# Ground_Station.net
KiCad netlist of a schematic drawn in EasyEDA
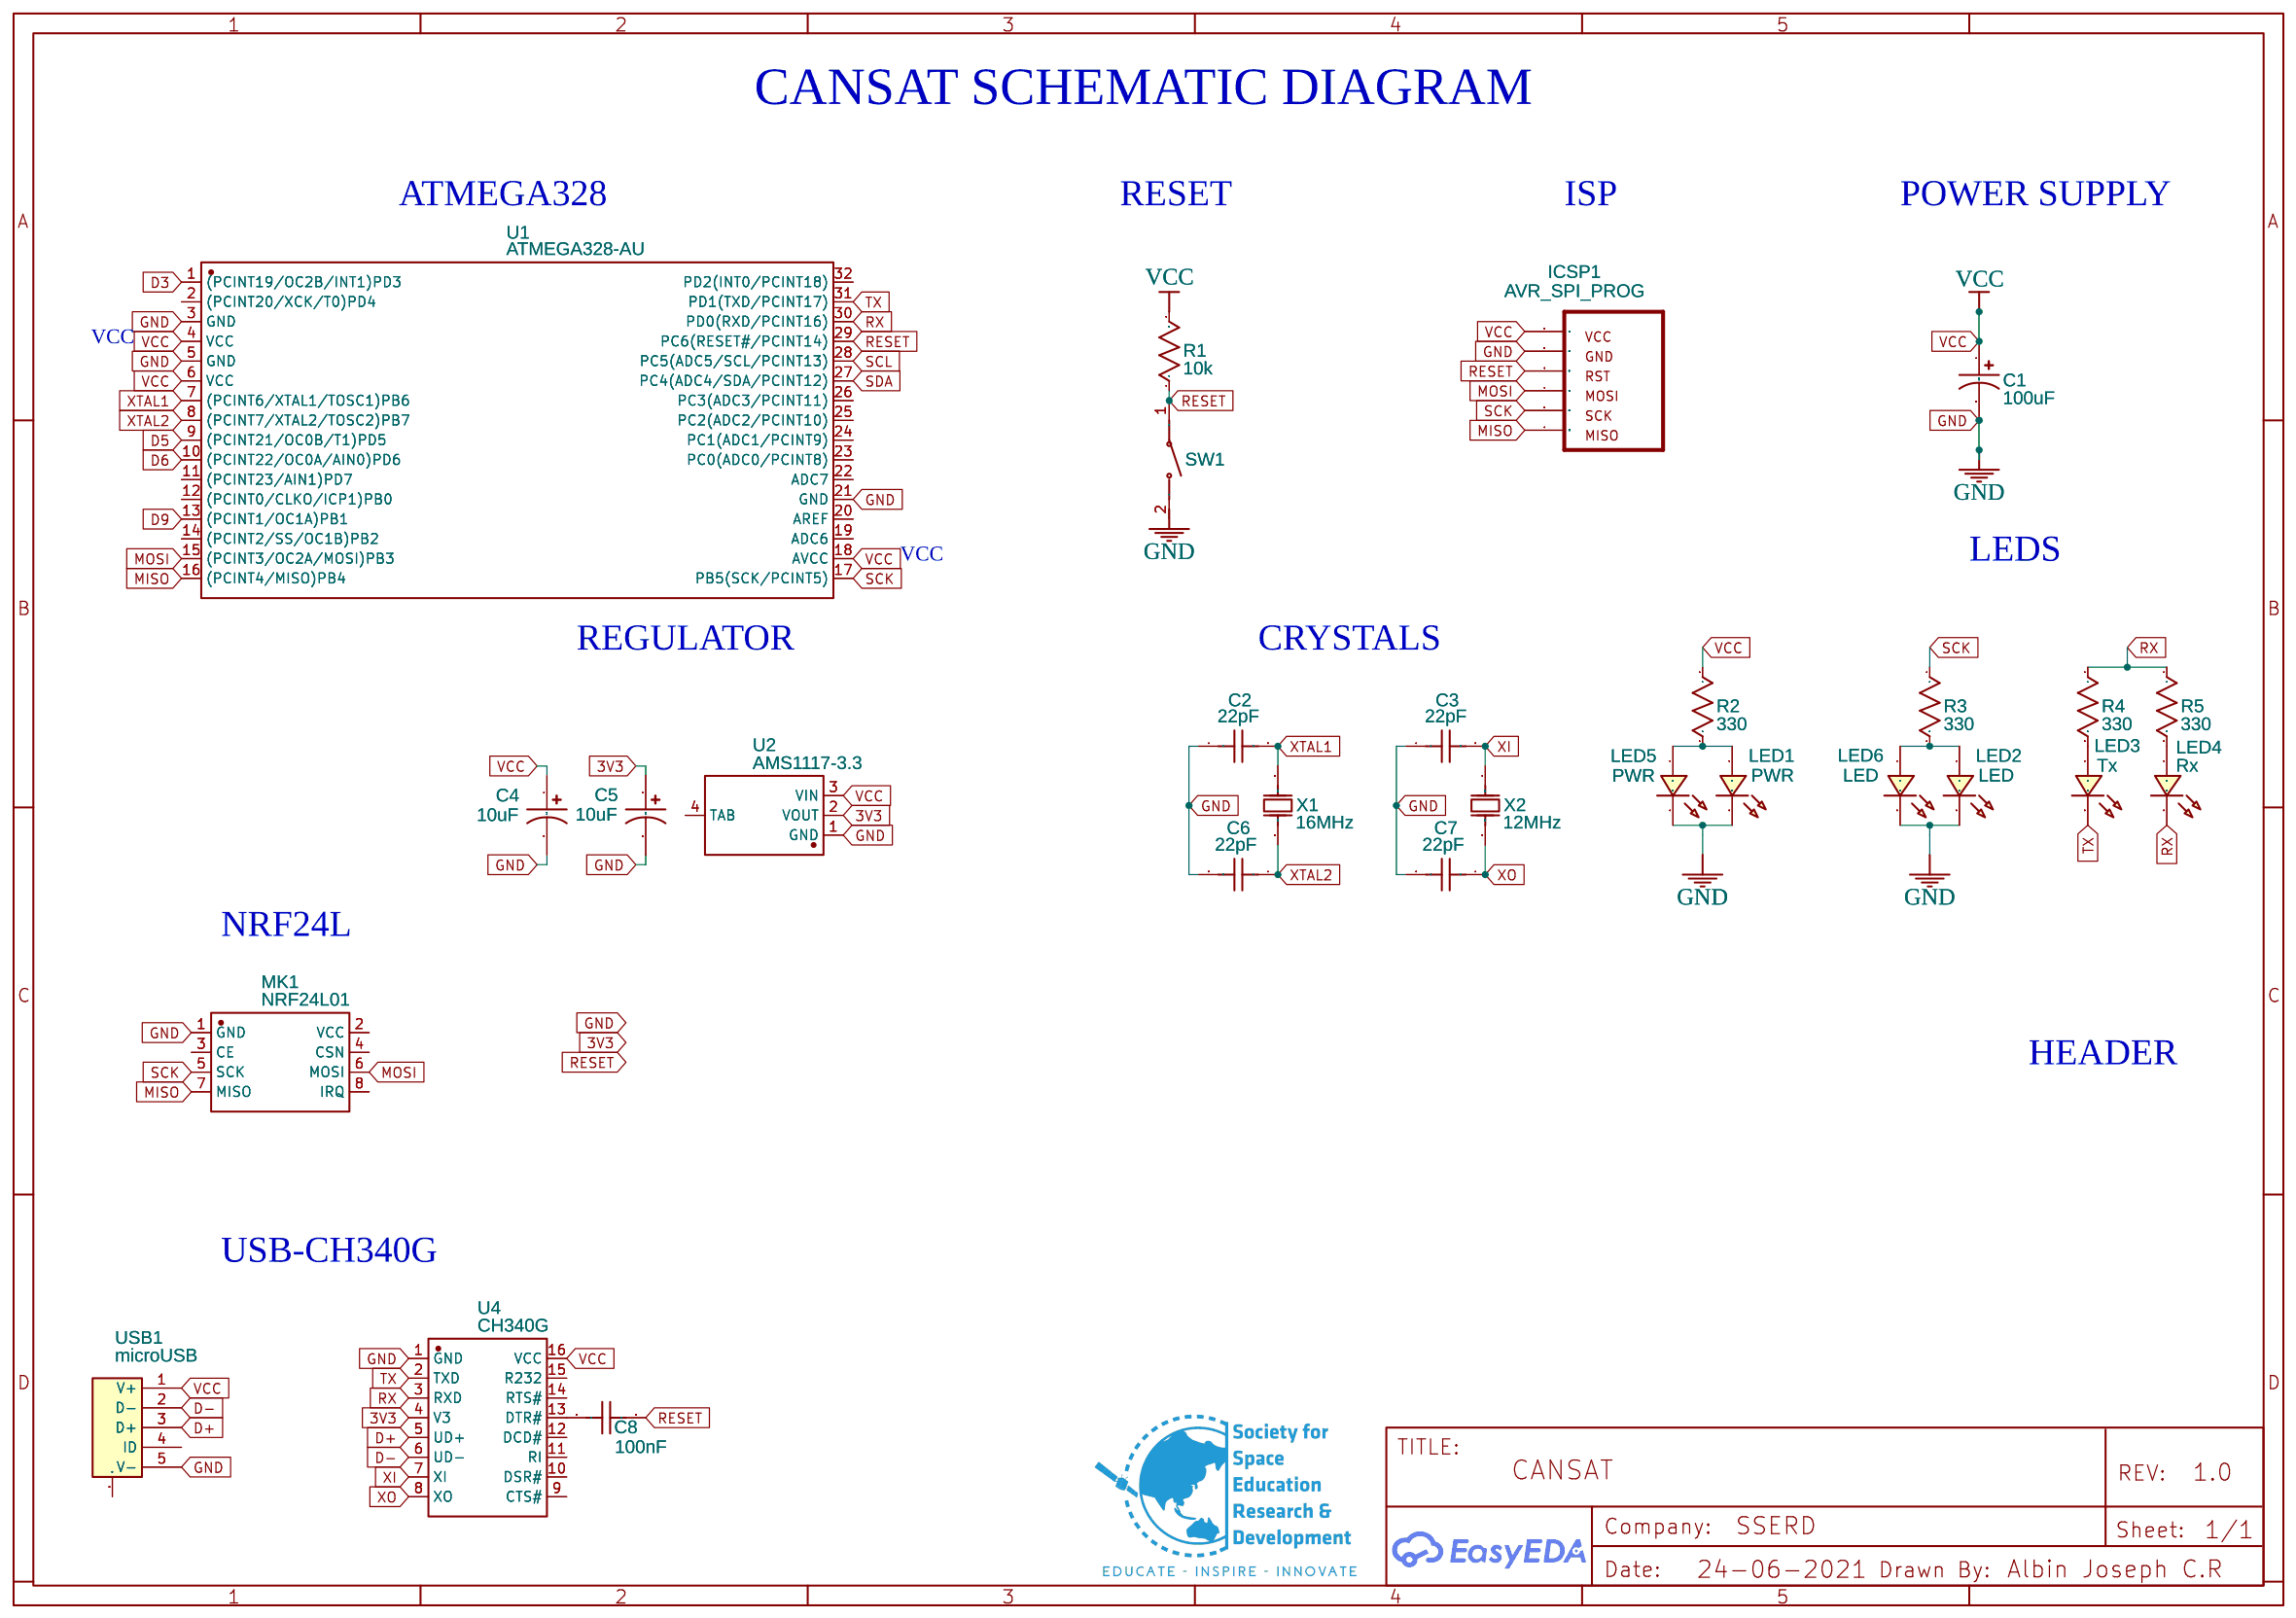
[diagram p0: schematic sheet]

(export (version "E")
  (design (tool "Eeschema 10.0.6"))
  (components
    (comp (ref "C1") (value "100uF") (libsource (lib "") (part "CE_TH_D4.0×F1.5_US")))
    (comp (ref "C2")
      (value "22pF")
      (fields
        (field (name "BOM_Manufacturer Part") "CC1H0R5CA1BDCH4B10MF")
        (field (name "BOM_Supplier Part") "C254078")
      )
      (libsource (lib "") (part "CC1H0R5CA1BDCH4B10MF_1"))
    )
    (comp (ref "C3")
      (value "22pF")
      (fields
        (field (name "BOM_Manufacturer Part") "CC1H0R5CA1BDCH4B10MF")
        (field (name "BOM_Supplier Part") "C254078")
      )
      (libsource (lib "") (part "CC1H0R5CA1BDCH4B10MF_1"))
    )
    (comp (ref "C4") (value "10uF") (libsource (lib "") (part "CE_TH_D4.0×F1.5_US")))
    (comp (ref "C5") (value "10uF") (libsource (lib "") (part "CE_TH_D4.0×F1.5_US")))
    (comp (ref "C6")
      (value "22pF")
      (fields
        (field (name "BOM_Manufacturer Part") "CC1H0R5CA1BDCH4B10MF")
        (field (name "BOM_Supplier Part") "C254078")
      )
      (libsource (lib "") (part "CC1H0R5CA1BDCH4B10MF"))
    )
    (comp (ref "C7")
      (value "22pF")
      (fields
        (field (name "BOM_Manufacturer Part") "CC1H0R5CA1BDCH4B10MF")
        (field (name "BOM_Supplier Part") "C254078")
      )
      (libsource (lib "") (part "CC1H0R5CA1BDCH4B10MF"))
    )
    (comp (ref "C8")
      (value "100nF")
      (fields
        (field (name "BOM_Manufacturer Part") "CC1H0R5CA1BDCH4B10MF")
        (field (name "BOM_Supplier Part") "C254078")
      )
      (libsource (lib "") (part "CC1H0R5CA1BDCH4B10MF_1"))
    )
    (comp (ref "ICSP1") (value "AVR_SPI_PROG") (libsource (lib "") (part "PA_AVR_SPI_PROGRAMMER_ARDUINO")))
    (comp (ref "LED1")
      (value "PWR")
      (fields (field (name "BOM_Manufacturer Part") "NCD0805G1") (field (name "BOM_Supplier Part") "C84260"))
      (libsource (lib "") (part "LED-0805_G"))
    )
    (comp (ref "LED2")
      (value "LED")
      (fields (field (name "BOM_Manufacturer Part") "NCD0805G1") (field (name "BOM_Supplier Part") "C84260"))
      (libsource (lib "") (part "LED-0805_G"))
    )
    (comp (ref "LED3")
      (value "Tx")
      (fields
        (field (name "BOM_Manufacturer Part") "D-B080508B1-KS2")
        (field (name "BOM_Supplier Part") "C108412")
      )
      (libsource (lib "") (part "LED-0805_B"))
    )
    (comp (ref "LED4")
      (value "Rx")
      (fields
        (field (name "BOM_Manufacturer Part") "D-B080508B1-KS2")
        (field (name "BOM_Supplier Part") "C108412")
      )
      (libsource (lib "") (part "LED-0805_B"))
    )
    (comp (ref "LED5")
      (value "PWR")
      (fields
        (field (name "BOM_Manufacturer Part") "204-10SYGD/S530-E3")
        (field (name "BOM_Supplier Part") "C85161")
      )
      (libsource (lib "") (part "LED-TH-3mm_G"))
    )
    (comp (ref "LED6")
      (value "LED")
      (fields
        (field (name "BOM_Manufacturer Part") "204-10SYGD/S530-E3")
        (field (name "BOM_Supplier Part") "C85161")
      )
      (libsource (lib "") (part "LED-TH-3mm_G"))
    )
    (comp (ref "MK1")
      (value "NRF24L01")
      (fields
        (field (name "BOM_Manufacturer Part") "NRF24L01+功率加强版绑定2.4Gwireless module")
        (field (name "BOM_Supplier Part") "C90751")
      )
      (libsource (lib "") (part "NRF24L01"))
    )
    (comp (ref "R1") (value "10k") (libsource (lib "") (part "R_AXIAL-0.4_US")))
    (comp (ref "R2") (value "330") (libsource (lib "") (part "R_AXIAL-0.4_US_1")))
    (comp (ref "R3") (value "330") (libsource (lib "") (part "R_AXIAL-0.4_US_1")))
    (comp (ref "R4") (value "330") (libsource (lib "") (part "R_AXIAL-0.4_US_1")))
    (comp (ref "R5") (value "330") (libsource (lib "") (part "R_AXIAL-0.4_US_1")))
    (comp (ref "SW1")
      (value "SWITCH,3*6*2.5")
      (fields
        (field (name "BOM_Manufacturer Part") "Switch,3*6*5Plastic head white,260G, 0.25mm,SMD")
        (field (name "BOM_Supplier Part") "C71855")
      )
      (libsource (lib "") (part "SWITCH,3*6*5PLASTIC HEAD WHITE,260G, 0.25MM,SMD"))
    )
    (comp (ref "U1")
      (value "ATMEGA328-AU")
      (fields (field (name "BOM_Supplier Part") "C618731"))
      (libsource (lib "") (part "ATMEGA328-AU"))
    )
    (comp (ref "U2")
      (value "AMS1117-3.3")
      (fields
        (field (name "BOM_Manufacturer Part") "AMS1117-1.8")
        (field (name "BOM_Supplier Part") "C498120")
      )
      (libsource (lib "") (part "AMS1117-1.8_C498120"))
    )
    (comp (ref "U4")
      (value "CH340G")
      (fields (field (name "BOM_Supplier Part") "C14267"))
      (libsource (lib "") (part "CH340G"))
    )
    (comp (ref "USB1")
      (value "microUSB")
      (fields
        (field (name "BOM_Manufacturer Part") "micro USBFemale")
        (field (name "BOM_Supplier Part") "C10418")
      )
      (libsource (lib "") (part "micro USBFemale"))
    )
    (comp (ref "X1")
      (value "16MHz")
      (fields
        (field (name "BOM_Manufacturer Part") "9AC10000202060")
        (field (name "BOM_Supplier Part") "C1508959")
      )
      (libsource (lib "") (part "9AC10000202060"))
    )
    (comp (ref "X2")
      (value "12MHz")
      (fields
        (field (name "BOM_Manufacturer Part") "9AC10000202060")
        (field (name "BOM_Supplier Part") "C1508959")
      )
      (libsource (lib "") (part "9AC10000202060"))
    )
  )
  (nets
    (net (code "1") (name "3V3") (class "Default")
      (node (ref "C5") (pin "1") (pinfunction "1_1") (pintype "unspecified"))
      (node (ref "U2") (pin "2") (pinfunction "VOUT_2") (pintype "unspecified"))
      (node (ref "U4") (pin "4") (pinfunction "V3_4") (pintype "unspecified"))
    )
    (net (code "2") (name "D+") (class "Default")
      (node (ref "U4") (pin "5") (pinfunction "UD+_5") (pintype "unspecified"))
      (node (ref "USB1") (pin "3") (pinfunction "D+_3") (pintype "unspecified"))
    )
    (net (code "3") (name "D-") (class "Default")
      (node (ref "U4") (pin "6") (pinfunction "UD-_6") (pintype "unspecified"))
      (node (ref "USB1") (pin "2") (pinfunction "D-_2") (pintype "unspecified"))
    )
    (net (code "4") (name "D3") (class "Default")
      (node (ref "U1") (pin "1") (pinfunction "(PCINT19/OC2B/INT1)PD3_1") (pintype "unspecified"))
    )
    (net (code "5") (name "D5") (class "Default")
      (node (ref "U1") (pin "9") (pinfunction "(PCINT21/OC0B/T1)PD5_9") (pintype "unspecified"))
    )
    (net (code "6") (name "D6") (class "Default")
      (node (ref "U1") (pin "10") (pinfunction "(PCINT22/OC0A/AIN0)PD6_10") (pintype "unspecified"))
    )
    (net (code "7") (name "D9") (class "Default")
      (node (ref "U1") (pin "13") (pinfunction "(PCINT1/OC1A)PB1_13") (pintype "unspecified"))
    )
    (net (code "8") (name "GND") (class "Default")
      (node (ref "C1") (pin "2") (pinfunction "2_2") (pintype "unspecified"))
      (node (ref "C2") (pin "1") (pinfunction "1_1") (pintype "unspecified"))
      (node (ref "C3") (pin "1") (pinfunction "1_1") (pintype "unspecified"))
      (node (ref "C4") (pin "2") (pinfunction "2_2") (pintype "unspecified"))
      (node (ref "C5") (pin "2") (pinfunction "2_2") (pintype "unspecified"))
      (node (ref "C6") (pin "2") (pinfunction "2_2") (pintype "unspecified"))
      (node (ref "C7") (pin "2") (pinfunction "2_2") (pintype "unspecified"))
      (node (ref "ICSP1") (pin "6") (pinfunction "GND_6") (pintype "unspecified"))
      (node (ref "LED1") (pin "2") (pinfunction "2_2") (pintype "unspecified"))
      (node (ref "LED2") (pin "2") (pinfunction "2_2") (pintype "unspecified"))
      (node (ref "LED5") (pin "2") (pinfunction "2_2") (pintype "unspecified"))
      (node (ref "LED6") (pin "2") (pinfunction "2_2") (pintype "unspecified"))
      (node (ref "MK1") (pin "1") (pinfunction "GND_1") (pintype "unspecified"))
      (node (ref "SW1") (pin "2") (pinfunction "2_2") (pintype "unspecified"))
      (node (ref "U1") (pin "21") (pinfunction "GND_21") (pintype "unspecified"))
      (node (ref "U1") (pin "3") (pinfunction "GND_3") (pintype "unspecified"))
      (node (ref "U1") (pin "5") (pinfunction "GND_5") (pintype "unspecified"))
      (node (ref "U2") (pin "1") (pinfunction "GND_1") (pintype "unspecified"))
      (node (ref "U4") (pin "1") (pinfunction "GND_1") (pintype "unspecified"))
      (node (ref "USB1") (pin "5") (pinfunction "V-_5") (pintype "unspecified"))
    )
    (net (code "9") (name "MISO") (class "Default")
      (node (ref "ICSP1") (pin "1") (pinfunction "MISO_1") (pintype "unspecified"))
      (node (ref "MK1") (pin "7") (pinfunction "MISO_7") (pintype "unspecified"))
      (node (ref "U1") (pin "16") (pinfunction "(PCINT4/MISO)PB4_16") (pintype "unspecified"))
    )
    (net (code "10") (name "MOSI") (class "Default")
      (node (ref "ICSP1") (pin "4") (pinfunction "MOSI_4") (pintype "unspecified"))
      (node (ref "MK1") (pin "6") (pinfunction "MOSI_6") (pintype "unspecified"))
      (node (ref "U1") (pin "15") (pinfunction "(PCINT3/OC2A/MOSI)PB3_15") (pintype "unspecified"))
    )
    (net (code "11") (name "Net-(LED1-Pad1)") (class "Default")
      (node (ref "LED1") (pin "1") (pinfunction "1_1") (pintype "unspecified"))
      (node (ref "LED5") (pin "1") (pinfunction "1_1") (pintype "unspecified"))
      (node (ref "R2") (pin "2") (pinfunction "2_2") (pintype "unspecified"))
    )
    (net (code "12") (name "Net-(LED2-Pad1)") (class "Default")
      (node (ref "LED2") (pin "1") (pinfunction "1_1") (pintype "unspecified"))
      (node (ref "LED6") (pin "1") (pinfunction "1_1") (pintype "unspecified"))
      (node (ref "R3") (pin "2") (pinfunction "2_2") (pintype "unspecified"))
    )
    (net (code "13") (name "Net-(LED3-Pad1)") (class "Default")
      (node (ref "LED3") (pin "1") (pinfunction "1_1") (pintype "unspecified"))
      (node (ref "R4") (pin "2") (pinfunction "2_2") (pintype "unspecified"))
    )
    (net (code "14") (name "Net-(LED4-Pad1)") (class "Default")
      (node (ref "LED4") (pin "1") (pinfunction "1_1") (pintype "unspecified"))
      (node (ref "R5") (pin "2") (pinfunction "2_2") (pintype "unspecified"))
    )
    (net (code "15") (name "Net-(U4-DTR#)") (class "Default")
      (node (ref "C8") (pin "1") (pinfunction "1_1") (pintype "unspecified"))
      (node (ref "U4") (pin "13") (pinfunction "DTR#_13") (pintype "unspecified"))
    )
    (net (code "16") (name "RESET") (class "Default")
      (node (ref "C8") (pin "2") (pinfunction "2_2") (pintype "unspecified"))
      (node (ref "ICSP1") (pin "5") (pinfunction "RST_5") (pintype "unspecified"))
      (node (ref "R1") (pin "1") (pinfunction "1_1") (pintype "unspecified"))
      (node (ref "SW1") (pin "1") (pinfunction "1_1") (pintype "unspecified"))
      (node (ref "U1") (pin "29") (pinfunction "PC6(RESET#/PCINT14)_29") (pintype "unspecified"))
    )
    (net (code "17") (name "RX") (class "Default")
      (node (ref "LED4") (pin "2") (pinfunction "2_2") (pintype "unspecified"))
      (node (ref "R4") (pin "1") (pinfunction "1_1") (pintype "unspecified"))
      (node (ref "R5") (pin "1") (pinfunction "1_1") (pintype "unspecified"))
      (node (ref "U1") (pin "30") (pinfunction "PD0(RXD/PCINT16)_30") (pintype "unspecified"))
      (node (ref "U4") (pin "3") (pinfunction "RXD_3") (pintype "unspecified"))
    )
    (net (code "18") (name "SCK") (class "Default")
      (node (ref "ICSP1") (pin "3") (pinfunction "SCK_3") (pintype "unspecified"))
      (node (ref "MK1") (pin "5") (pinfunction "SCK_5") (pintype "unspecified"))
      (node (ref "R3") (pin "1") (pinfunction "1_1") (pintype "unspecified"))
      (node (ref "U1") (pin "17") (pinfunction "PB5(SCK/PCINT5)_17") (pintype "unspecified"))
    )
    (net (code "19") (name "SCL") (class "Default")
      (node (ref "U1") (pin "28") (pinfunction "PC5(ADC5/SCL/PCINT13)_28") (pintype "unspecified"))
    )
    (net (code "20") (name "SDA") (class "Default")
      (node (ref "U1") (pin "27") (pinfunction "PC4(ADC4/SDA/PCINT12)_27") (pintype "unspecified"))
    )
    (net (code "21") (name "TX") (class "Default")
      (node (ref "LED3") (pin "2") (pinfunction "2_2") (pintype "unspecified"))
      (node (ref "U1") (pin "31") (pinfunction "PD1(TXD/PCINT17)_31") (pintype "unspecified"))
      (node (ref "U4") (pin "2") (pinfunction "TXD_2") (pintype "unspecified"))
    )
    (net (code "22") (name "VCC") (class "Default")
      (node (ref "C1") (pin "1") (pinfunction "1_1") (pintype "unspecified"))
      (node (ref "C4") (pin "1") (pinfunction "1_1") (pintype "unspecified"))
      (node (ref "ICSP1") (pin "2") (pinfunction "VCC_2") (pintype "unspecified"))
      (node (ref "R1") (pin "2") (pinfunction "2_2") (pintype "unspecified"))
      (node (ref "R2") (pin "1") (pinfunction "1_1") (pintype "unspecified"))
      (node (ref "U1") (pin "18") (pinfunction "AVCC_18") (pintype "unspecified"))
      (node (ref "U1") (pin "4") (pinfunction "VCC_4") (pintype "unspecified"))
      (node (ref "U1") (pin "6") (pinfunction "VCC_6") (pintype "unspecified"))
      (node (ref "U2") (pin "3") (pinfunction "VIN_3") (pintype "unspecified"))
      (node (ref "U4") (pin "16") (pinfunction "VCC_16") (pintype "unspecified"))
      (node (ref "USB1") (pin "1") (pinfunction "V+_1") (pintype "unspecified"))
    )
    (net (code "23") (name "XI") (class "Default")
      (node (ref "C3") (pin "2") (pinfunction "2_2") (pintype "unspecified"))
      (node (ref "U4") (pin "7") (pinfunction "XI_7") (pintype "unspecified"))
      (node (ref "X2") (pin "1") (pinfunction "OSC1_1") (pintype "input"))
    )
    (net (code "24") (name "XO") (class "Default")
      (node (ref "C7") (pin "1") (pinfunction "1_1") (pintype "unspecified"))
      (node (ref "U4") (pin "8") (pinfunction "XO_8") (pintype "unspecified"))
      (node (ref "X2") (pin "2") (pinfunction "OSC2_2") (pintype "input"))
    )
    (net (code "25") (name "XTAL1") (class "Default")
      (node (ref "C2") (pin "2") (pinfunction "2_2") (pintype "unspecified"))
      (node (ref "U1") (pin "7") (pinfunction "(PCINT6/XTAL1/TOSC1)PB6_7") (pintype "unspecified"))
      (node (ref "X1") (pin "1") (pinfunction "OSC1_1") (pintype "input"))
    )
    (net (code "26") (name "XTAL2") (class "Default")
      (node (ref "C6") (pin "1") (pinfunction "1_1") (pintype "unspecified"))
      (node (ref "U1") (pin "8") (pinfunction "(PCINT7/XTAL2/TOSC2)PB7_8") (pintype "unspecified"))
      (node (ref "X1") (pin "2") (pinfunction "OSC2_2") (pintype "input"))
    )
    (net (code "27") (name "unconnected-(MK1-CE-Pad3)") (class "Default")
      (node (ref "MK1") (pin "3") (pinfunction "CE_3") (pintype "unspecified"))
    )
    (net (code "28") (name "unconnected-(MK1-CSN-Pad4)") (class "Default")
      (node (ref "MK1") (pin "4") (pinfunction "CSN_4") (pintype "unspecified"))
    )
    (net (code "29") (name "unconnected-(MK1-IRQ-Pad8)") (class "Default")
      (node (ref "MK1") (pin "8") (pinfunction "IRQ_8") (pintype "unspecified"))
    )
    (net (code "30") (name "unconnected-(MK1-VCC-Pad2)") (class "Default")
      (node (ref "MK1") (pin "2") (pinfunction "VCC_2") (pintype "unspecified"))
    )
    (net (code "31") (name "unconnected-(U1-(PCINT0{slash}CLKO{slash}ICP1)PB0-Pad12)") (class "Default")
      (node (ref "U1") (pin "12") (pinfunction "(PCINT0/CLKO/ICP1)PB0_12") (pintype "unspecified"))
    )
    (net (code "32") (name "unconnected-(U1-(PCINT2{slash}SS{slash}OC1B)PB2-Pad14)") (class "Default")
      (node (ref "U1") (pin "14") (pinfunction "(PCINT2/SS/OC1B)PB2_14") (pintype "unspecified"))
    )
    (net (code "33") (name "unconnected-(U1-(PCINT20{slash}XCK{slash}T0)PD4-Pad2)") (class "Default")
      (node (ref "U1") (pin "2") (pinfunction "(PCINT20/XCK/T0)PD4_2") (pintype "unspecified"))
    )
    (net (code "34") (name "unconnected-(U1-(PCINT23{slash}AIN1)PD7-Pad11)") (class "Default")
      (node (ref "U1") (pin "11") (pinfunction "(PCINT23/AIN1)PD7_11") (pintype "unspecified"))
    )
    (net (code "35") (name "unconnected-(U1-ADC6-Pad19)") (class "Default")
      (node (ref "U1") (pin "19") (pinfunction "ADC6_19") (pintype "unspecified"))
    )
    (net (code "36") (name "unconnected-(U1-ADC7-Pad22)") (class "Default")
      (node (ref "U1") (pin "22") (pinfunction "ADC7_22") (pintype "unspecified"))
    )
    (net (code "37") (name "unconnected-(U1-AREF-Pad20)") (class "Default")
      (node (ref "U1") (pin "20") (pinfunction "AREF_20") (pintype "unspecified"))
    )
    (net (code "38") (name "unconnected-(U1-PC0(ADC0{slash}PCINT8)-Pad23)") (class "Default")
      (node (ref "U1") (pin "23") (pinfunction "PC0(ADC0/PCINT8)_23") (pintype "unspecified"))
    )
    (net (code "39") (name "unconnected-(U1-PC1(ADC1{slash}PCINT9)-Pad24)") (class "Default")
      (node (ref "U1") (pin "24") (pinfunction "PC1(ADC1/PCINT9)_24") (pintype "unspecified"))
    )
    (net (code "40") (name "unconnected-(U1-PC2(ADC2{slash}PCINT10)-Pad25)") (class "Default")
      (node (ref "U1") (pin "25") (pinfunction "PC2(ADC2/PCINT10)_25") (pintype "unspecified"))
    )
    (net (code "41") (name "unconnected-(U1-PC3(ADC3{slash}PCINT11)-Pad26)") (class "Default")
      (node (ref "U1") (pin "26") (pinfunction "PC3(ADC3/PCINT11)_26") (pintype "unspecified"))
    )
    (net (code "42") (name "unconnected-(U1-PD2(INT0{slash}PCINT18)-Pad32)") (class "Default")
      (node (ref "U1") (pin "32") (pinfunction "PD2(INT0/PCINT18)_32") (pintype "unspecified"))
    )
    (net (code "43") (name "unconnected-(U2-TAB-Pad4)") (class "Default")
      (node (ref "U2") (pin "4") (pinfunction "TAB_4") (pintype "unspecified"))
    )
    (net (code "44") (name "unconnected-(U4-CTS#-Pad9)") (class "Default")
      (node (ref "U4") (pin "9") (pinfunction "CTS#_9") (pintype "unspecified"))
    )
    (net (code "45") (name "unconnected-(U4-DCD#-Pad12)") (class "Default")
      (node (ref "U4") (pin "12") (pinfunction "DCD#_12") (pintype "unspecified"))
    )
    (net (code "46") (name "unconnected-(U4-DSR#-Pad10)") (class "Default")
      (node (ref "U4") (pin "10") (pinfunction "DSR#_10") (pintype "unspecified"))
    )
    (net (code "47") (name "unconnected-(U4-R232-Pad15)") (class "Default")
      (node (ref "U4") (pin "15") (pinfunction "R232_15") (pintype "unspecified"))
    )
    (net (code "48") (name "unconnected-(U4-RI-Pad11)") (class "Default")
      (node (ref "U4") (pin "11") (pinfunction "RI_11") (pintype "unspecified"))
    )
    (net (code "49") (name "unconnected-(U4-RTS#-Pad14)") (class "Default")
      (node (ref "U4") (pin "14") (pinfunction "RTS#_14") (pintype "unspecified"))
    )
    (net (code "50") (name "unconnected-(USB1-ID-Pad4)") (class "Default")
      (node (ref "USB1") (pin "4") (pinfunction "ID_4") (pintype "unspecified"))
    )
    (net (code "51") (name "unconnected-(USB1-MTN-Pad0)") (class "Default")
      (node (ref "USB1") (pin "0") (pinfunction "MTN_0") (pintype "input"))
    )
  )
)
